# logger.net
KiCad netlist of a schematic drawn in EAGLE
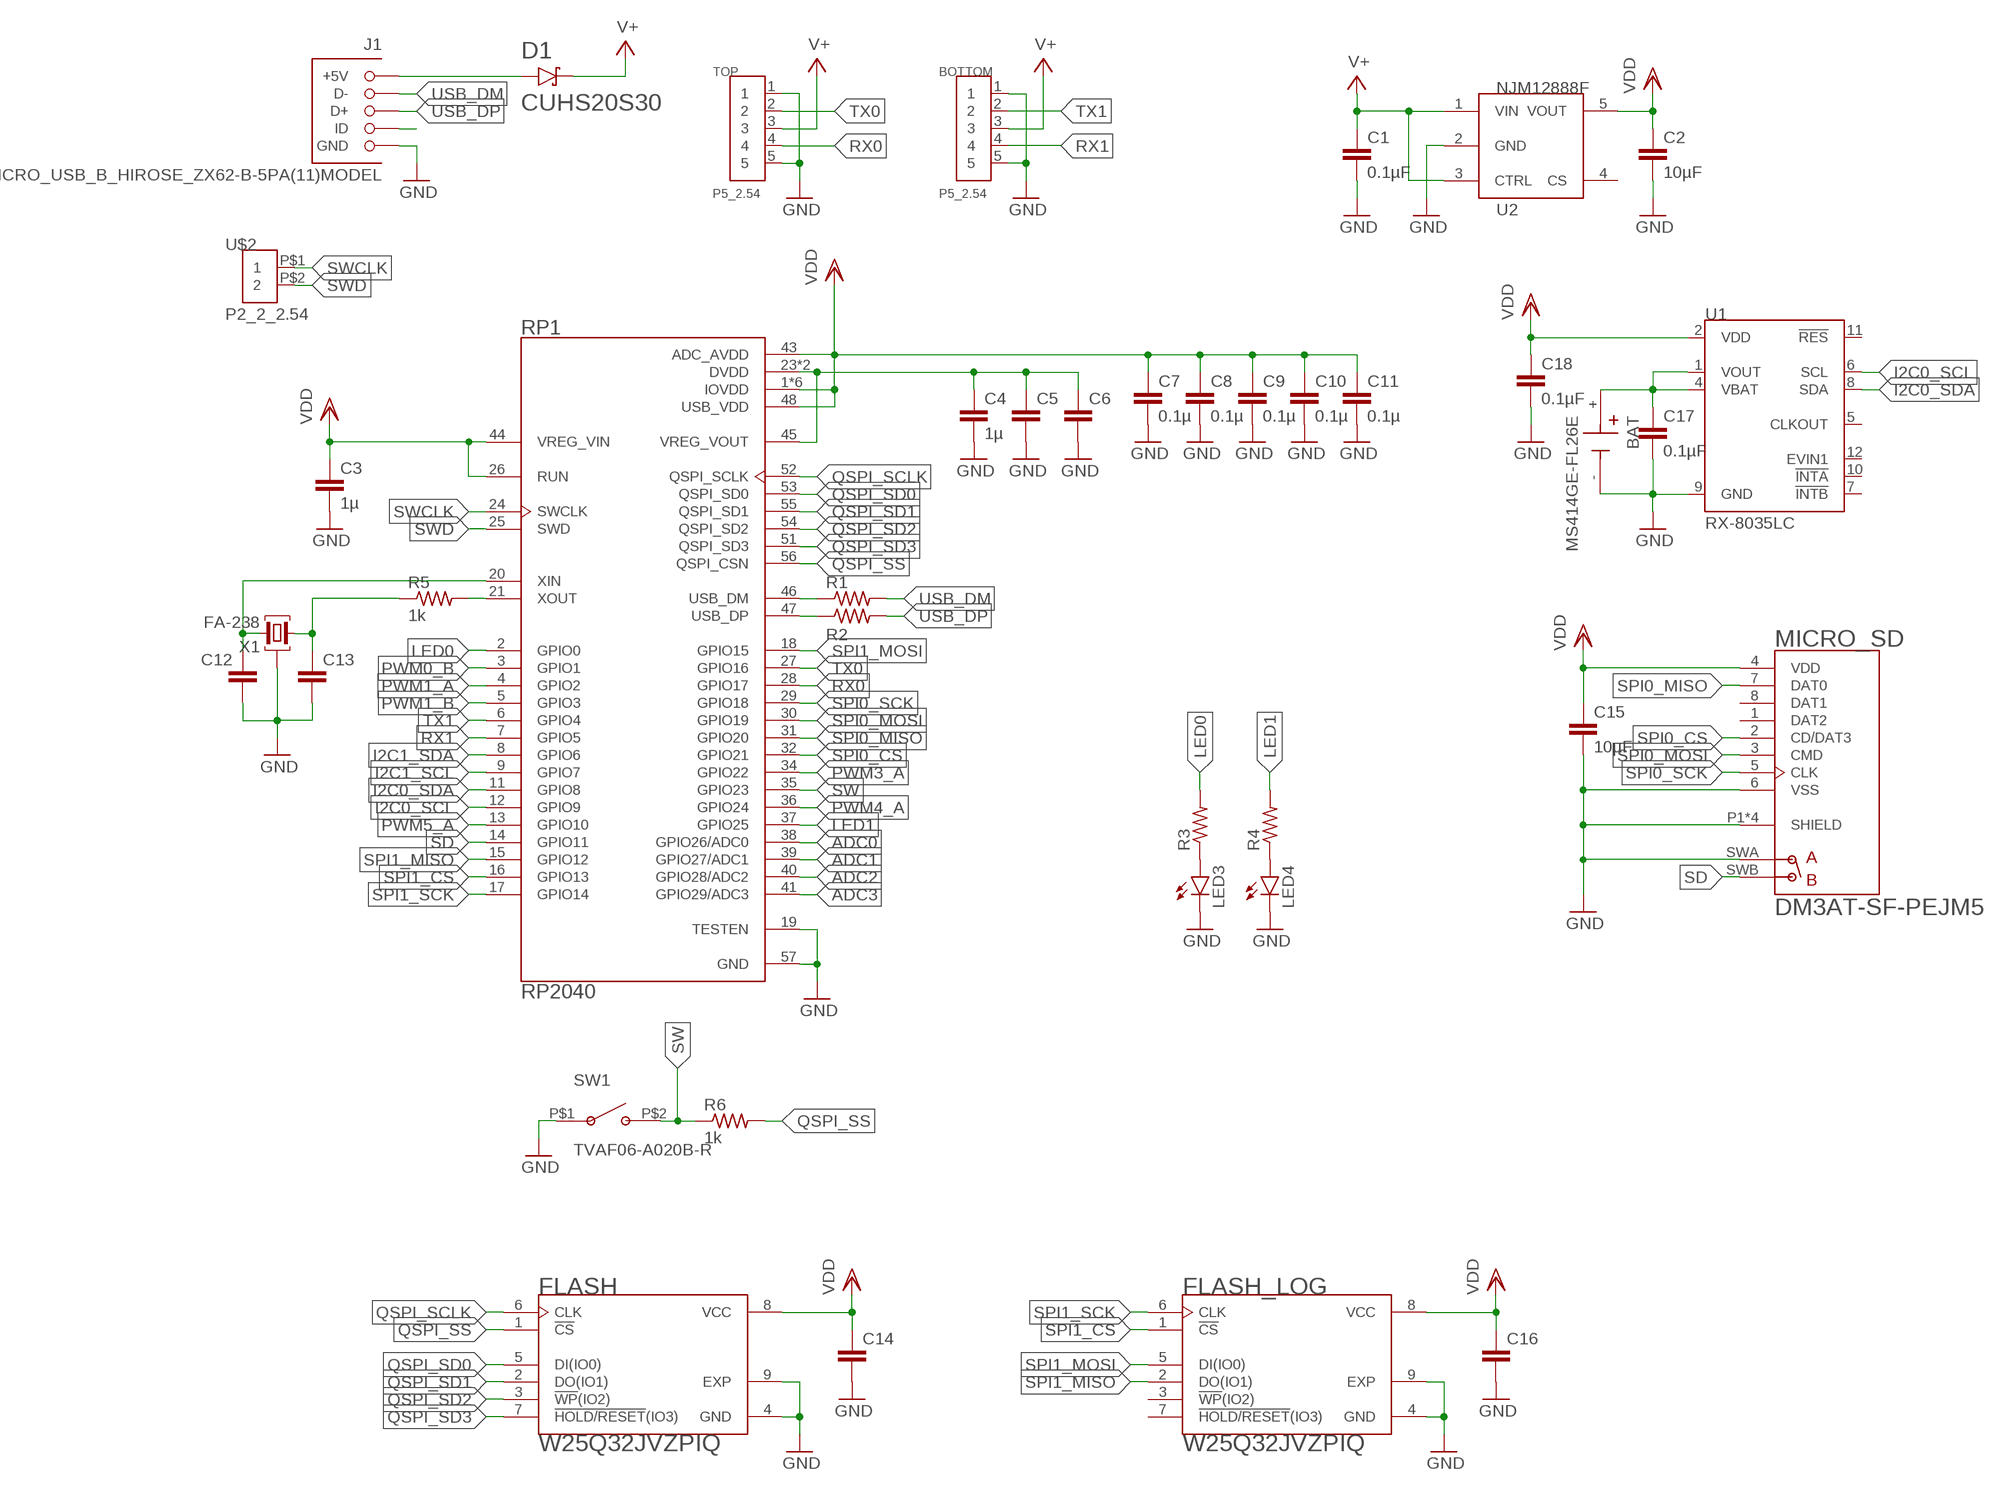
[diagram p0: schematic, sheet 1]

(export (version "E")
  (design (tool "Eeschema 10.0.6"))
  (components
    (comp (ref "BAT")
      (value "MS414GE-FL26E")
      (footprint "eagle-import:BAT_MS414GE-FL26E")
      (fields (field (name "MF") "Seiko"))
      (libsource (lib "eagle-import") (part "MS414GE-FL26E"))
    )
    (comp (ref "BOTTOM")
      (value "P5_2.54")
      (footprint "eagle-import:P5_2.54")
      (libsource (lib "eagle-import") (part "P5_2.54"))
    )
    (comp (ref "C1")
      (value "0.1µF")
      (footprint "eagle-import:C0402")
      (libsource (lib "eagle-import") (part "C-EUC0402"))
    )
    (comp (ref "C2")
      (value "10µF")
      (footprint "eagle-import:C0402")
      (libsource (lib "eagle-import") (part "C-EUC0402"))
    )
    (comp (ref "C3")
      (value "1µ")
      (footprint "eagle-import:C0402")
      (libsource (lib "eagle-import") (part "C-EUC0402"))
    )
    (comp (ref "C4")
      (value "1µ")
      (footprint "eagle-import:C0402")
      (libsource (lib "eagle-import") (part "C-EUC0402"))
    )
    (comp (ref "C5")
      (value "C-EUC0402")
      (footprint "eagle-import:C0402")
      (libsource (lib "eagle-import") (part "C-EUC0402"))
    )
    (comp (ref "C6")
      (value "C-EUC0402")
      (footprint "eagle-import:C0402")
      (libsource (lib "eagle-import") (part "C-EUC0402"))
    )
    (comp (ref "C7")
      (value "0.1µ")
      (footprint "eagle-import:C0402")
      (libsource (lib "eagle-import") (part "C-EUC0402"))
    )
    (comp (ref "C8")
      (value "0.1µ")
      (footprint "eagle-import:C0402")
      (libsource (lib "eagle-import") (part "C-EUC0402"))
    )
    (comp (ref "C9")
      (value "0.1µ")
      (footprint "eagle-import:C0402")
      (libsource (lib "eagle-import") (part "C-EUC0402"))
    )
    (comp (ref "C10")
      (value "0.1µ")
      (footprint "eagle-import:C0402")
      (libsource (lib "eagle-import") (part "C-EUC0402"))
    )
    (comp (ref "C11")
      (value "0.1µ")
      (footprint "eagle-import:C0402")
      (libsource (lib "eagle-import") (part "C-EUC0402"))
    )
    (comp (ref "C12")
      (value "C-EUC0402")
      (footprint "eagle-import:C0402")
      (libsource (lib "eagle-import") (part "C-EUC0402"))
    )
    (comp (ref "C13")
      (value "C-EUC0402")
      (footprint "eagle-import:C0402")
      (libsource (lib "eagle-import") (part "C-EUC0402"))
    )
    (comp (ref "C14")
      (value "C-EUC0402")
      (footprint "eagle-import:C0402")
      (libsource (lib "eagle-import") (part "C-EUC0402"))
    )
    (comp (ref "C15")
      (value "10µF")
      (footprint "eagle-import:C0402")
      (libsource (lib "eagle-import") (part "C-EUC0402"))
    )
    (comp (ref "C16")
      (value "C-EUC0402")
      (footprint "eagle-import:C0402")
      (libsource (lib "eagle-import") (part "C-EUC0402"))
    )
    (comp (ref "C17")
      (value "0.1µF")
      (footprint "eagle-import:C0402")
      (libsource (lib "eagle-import") (part "C-EUC0402"))
    )
    (comp (ref "C18")
      (value "0.1µF")
      (footprint "eagle-import:C0402")
      (libsource (lib "eagle-import") (part "C-EUC0402"))
    )
    (comp (ref "D1")
      (value "CUHS20S30")
      (footprint "eagle-import:CUHS20S30")
      (libsource (lib "eagle-import") (part "CUHS20S30"))
    )
    (comp (ref "FLASH")
      (value "W25Q32JVZPIQ")
      (footprint "eagle-import:SON127P600X500X80-9N")
      (fields (field (name "MF") "Winbond"))
      (libsource (lib "eagle-import") (part "W25Q32JVZPIQ"))
    )
    (comp (ref "FLASH_LOG")
      (value "W25Q32JVZPIQ")
      (footprint "eagle-import:SON127P600X500X80-9N")
      (fields (field (name "MF") "Winbond"))
      (libsource (lib "eagle-import") (part "W25Q32JVZPIQ"))
    )
    (comp (ref "J1")
      (value "MICRO_USB_B_HIROSE_ZX62-B-5PA(11)MODEL")
      (footprint "eagle-import:GHI-CONNECTORS_10118192-0001LF(MICRO-USB-B-AMPHENOL-FCI)")
      (libsource (lib "eagle-import") (part "MICRO_USB_B_HIROSE_ZX62-B-5PA(11)MODEL"))
    )
    (comp (ref "LED3")
      (value "LEDCHIPLED_0603")
      (footprint "eagle-import:CHIPLED_0603")
      (libsource (lib "eagle-import") (part "LEDCHIPLED_0603"))
    )
    (comp (ref "LED4")
      (value "LEDCHIPLED_0603")
      (footprint "eagle-import:CHIPLED_0603")
      (libsource (lib "eagle-import") (part "LEDCHIPLED_0603"))
    )
    (comp (ref "MICRO_SD")
      (value "DM3AT-SF-PEJM5")
      (footprint "eagle-import:HRS_DM3AT-SF-PEJM5")
      (fields (field (name "DIGI-KEY_PART_NUMBER") "HR1964CT-ND") (field (name "MF") "Hirose"))
      (libsource (lib "eagle-import") (part "DM3AT-SF-PEJM5"))
    )
    (comp (ref "R1")
      (value "R-US_R0402")
      (footprint "eagle-import:R0402")
      (libsource (lib "eagle-import") (part "R-US_R0402"))
    )
    (comp (ref "R2")
      (value "R-US_R0402")
      (footprint "eagle-import:R0402")
      (libsource (lib "eagle-import") (part "R-US_R0402"))
    )
    (comp (ref "R3")
      (value "R-US_R0402")
      (footprint "eagle-import:R0402")
      (libsource (lib "eagle-import") (part "R-US_R0402"))
    )
    (comp (ref "R4")
      (value "R-US_R0402")
      (footprint "eagle-import:R0402")
      (libsource (lib "eagle-import") (part "R-US_R0402"))
    )
    (comp (ref "R5")
      (value "1k")
      (footprint "eagle-import:R0402")
      (libsource (lib "eagle-import") (part "R-US_R0402"))
    )
    (comp (ref "R6")
      (value "1k")
      (footprint "eagle-import:R0402")
      (libsource (lib "eagle-import") (part "R-US_R0402"))
    )
    (comp (ref "RP1")
      (value "RP2040")
      (footprint "eagle-import:QFN40P700X700X90-57N")
      (fields (field (name "MF") "Raspberry Pi"))
      (libsource (lib "eagle-import") (part "RP2040"))
    )
    (comp (ref "SW1")
      (value "TVAF06-A020B-R")
      (footprint "eagle-import:TVAF06-A020B-R")
      (libsource (lib "eagle-import") (part "TVAF06-A020B-R"))
    )
    (comp (ref "TOP")
      (value "P5_2.54")
      (footprint "eagle-import:P5_2.54")
      (libsource (lib "eagle-import") (part "P5_2.54"))
    )
    (comp (ref "U$2")
      (value "P2_2_2.54")
      (footprint "eagle-import:P2_2.54")
      (libsource (lib "eagle-import") (part "P2_2_2.54"))
    )
    (comp (ref "U1")
      (value "RX-8035LC")
      (footprint "eagle-import:VSOJ12")
      (libsource (lib "eagle-import") (part "RX-8035LC"))
    )
    (comp (ref "U2")
      (value "NJM12888F")
      (footprint "eagle-import:SOT95P240X110-5N")
      (libsource (lib "eagle-import") (part "NJM12888F"))
    )
    (comp (ref "X1")
      (value "FA-238")
      (footprint "eagle-import:FA-238")
      (libsource (lib "eagle-import") (part "FA-238"))
    )
  )
  (nets
    (net (code "1") (name "ADC0") (class "Default")
      (node (ref "RP1") (pin "38") (pinfunction "GPIO26/ADC0_38") (pintype "bidirectional"))
    )
    (net (code "2") (name "ADC1") (class "Default")
      (node (ref "RP1") (pin "39") (pinfunction "GPIO27/ADC1_39") (pintype "bidirectional"))
    )
    (net (code "3") (name "ADC2") (class "Default")
      (node (ref "RP1") (pin "40") (pinfunction "GPIO28/ADC2_40") (pintype "bidirectional"))
    )
    (net (code "4") (name "ADC3") (class "Default")
      (node (ref "RP1") (pin "41") (pinfunction "GPIO29/ADC3_41") (pintype "bidirectional"))
    )
    (net (code "5") (name "GND") (class "Default")
      (node (ref "BAT") (pin "-") (pinfunction "-_-") (pintype "passive"))
      (node (ref "BOTTOM") (pin "1") (pinfunction "1_1") (pintype "bidirectional"))
      (node (ref "BOTTOM") (pin "5") (pinfunction "5_5") (pintype "bidirectional"))
      (node (ref "C1") (pin "2") (pinfunction "2_2") (pintype "passive"))
      (node (ref "C10") (pin "2") (pinfunction "2_2") (pintype "passive"))
      (node (ref "C11") (pin "2") (pinfunction "2_2") (pintype "passive"))
      (node (ref "C12") (pin "2") (pinfunction "2_2") (pintype "passive"))
      (node (ref "C13") (pin "2") (pinfunction "2_2") (pintype "passive"))
      (node (ref "C14") (pin "2") (pinfunction "2_2") (pintype "passive"))
      (node (ref "C15") (pin "2") (pinfunction "2_2") (pintype "passive"))
      (node (ref "C16") (pin "2") (pinfunction "2_2") (pintype "passive"))
      (node (ref "C17") (pin "2") (pinfunction "2_2") (pintype "passive"))
      (node (ref "C18") (pin "2") (pinfunction "2_2") (pintype "passive"))
      (node (ref "C2") (pin "2") (pinfunction "2_2") (pintype "passive"))
      (node (ref "C3") (pin "2") (pinfunction "2_2") (pintype "passive"))
      (node (ref "C4") (pin "2") (pinfunction "2_2") (pintype "passive"))
      (node (ref "C5") (pin "2") (pinfunction "2_2") (pintype "passive"))
      (node (ref "C6") (pin "2") (pinfunction "2_2") (pintype "passive"))
      (node (ref "C7") (pin "2") (pinfunction "2_2") (pintype "passive"))
      (node (ref "C8") (pin "2") (pinfunction "2_2") (pintype "passive"))
      (node (ref "C9") (pin "2") (pinfunction "2_2") (pintype "passive"))
      (node (ref "FLASH") (pin "4") (pinfunction "GND_4") (pintype "power_in"))
      (node (ref "FLASH") (pin "9") (pinfunction "EXP_9") (pintype "passive"))
      (node (ref "FLASH_LOG") (pin "4") (pinfunction "GND_4") (pintype "power_in"))
      (node (ref "FLASH_LOG") (pin "9") (pinfunction "EXP_9") (pintype "passive"))
      (node (ref "J1") (pin "CGND1") (pinfunction "GND_CGND1") (pintype "bidirectional"))
      (node (ref "J1") (pin "CGND2") (pinfunction "GND_CGND2") (pintype "bidirectional"))
      (node (ref "J1") (pin "CGND3") (pinfunction "GND_CGND3") (pintype "bidirectional"))
      (node (ref "J1") (pin "CGND4") (pinfunction "GND_CGND4") (pintype "bidirectional"))
      (node (ref "J1") (pin "CGND5") (pinfunction "GND_CGND5") (pintype "bidirectional"))
      (node (ref "J1") (pin "CGND6") (pinfunction "GND_CGND6") (pintype "bidirectional"))
      (node (ref "J1") (pin "GND") (pinfunction "GND_GND") (pintype "bidirectional"))
      (node (ref "LED3") (pin "C") (pinfunction "C_C") (pintype "passive"))
      (node (ref "LED4") (pin "C") (pinfunction "C_C") (pintype "passive"))
      (node (ref "MICRO_SD") (pin "6") (pinfunction "VSS_6") (pintype "power_in"))
      (node (ref "MICRO_SD") (pin "P1") (pinfunction "SHIELD_P1") (pintype "passive"))
      (node (ref "MICRO_SD") (pin "P2") (pinfunction "SHIELD_P2") (pintype "passive"))
      (node (ref "MICRO_SD") (pin "P3") (pinfunction "SHIELD_P3") (pintype "passive"))
      (node (ref "MICRO_SD") (pin "P4") (pinfunction "SHIELD_P4") (pintype "passive"))
      (node (ref "MICRO_SD") (pin "SWA") (pinfunction "A_SWA") (pintype "bidirectional"))
      (node (ref "RP1") (pin "19") (pinfunction "TESTEN_19") (pintype "passive"))
      (node (ref "RP1") (pin "57") (pinfunction "GND_57") (pintype "power_in"))
      (node (ref "SW1") (pin "P$1") (pinfunction "A_P$1") (pintype "bidirectional"))
      (node (ref "TOP") (pin "1") (pinfunction "1_1") (pintype "bidirectional"))
      (node (ref "TOP") (pin "5") (pinfunction "5_5") (pintype "bidirectional"))
      (node (ref "U1") (pin "9") (pinfunction "GND_9") (pintype "power_in"))
      (node (ref "U2") (pin "2") (pinfunction "GND_2") (pintype "power_in"))
      (node (ref "X1") (pin "2") (pinfunction "G_2") (pintype "passive"))
      (node (ref "X1") (pin "4") (pinfunction "G_4") (pintype "passive"))
    )
    (net (code "6") (name "I2C0_SCL") (class "Default")
      (node (ref "RP1") (pin "12") (pinfunction "GPIO9_12") (pintype "bidirectional"))
      (node (ref "U1") (pin "6") (pinfunction "SCL_6") (pintype "input"))
    )
    (net (code "7") (name "I2C0_SDA") (class "Default")
      (node (ref "RP1") (pin "11") (pinfunction "GPIO8_11") (pintype "bidirectional"))
      (node (ref "U1") (pin "8") (pinfunction "SDA_8") (pintype "bidirectional"))
    )
    (net (code "8") (name "I2C1_SCL") (class "Default")
      (node (ref "RP1") (pin "9") (pinfunction "GPIO7_9") (pintype "bidirectional"))
    )
    (net (code "9") (name "I2C1_SDA") (class "Default")
      (node (ref "RP1") (pin "8") (pinfunction "GPIO6_8") (pintype "bidirectional"))
    )
    (net (code "10") (name "LED0") (class "Default")
      (node (ref "R3") (pin "2") (pinfunction "2_2") (pintype "passive"))
      (node (ref "RP1") (pin "2") (pinfunction "GPIO0_2") (pintype "bidirectional"))
    )
    (net (code "11") (name "LED1") (class "Default")
      (node (ref "R4") (pin "2") (pinfunction "2_2") (pintype "passive"))
      (node (ref "RP1") (pin "37") (pinfunction "GPIO25_37") (pintype "bidirectional"))
    )
    (net (code "12") (name "Net-(C13-Pad1)") (class "Default")
      (node (ref "C13") (pin "1") (pinfunction "1_1") (pintype "passive"))
      (node (ref "R5") (pin "1") (pinfunction "1_1") (pintype "passive"))
      (node (ref "X1") (pin "1") (pinfunction "1_1") (pintype "passive"))
    )
    (net (code "13") (name "Net-(J1-+5V)") (class "Default")
      (node (ref "D1") (pin "A") (pinfunction "A_A") (pintype "bidirectional"))
      (node (ref "J1") (pin "VBUS") (pinfunction "+5V_VBUS") (pintype "bidirectional"))
    )
    (net (code "14") (name "Net-(LED3-PadA)") (class "Default")
      (node (ref "LED3") (pin "A") (pinfunction "A_A") (pintype "passive"))
      (node (ref "R3") (pin "1") (pinfunction "1_1") (pintype "passive"))
    )
    (net (code "15") (name "Net-(LED4-PadA)") (class "Default")
      (node (ref "LED4") (pin "A") (pinfunction "A_A") (pintype "passive"))
      (node (ref "R4") (pin "1") (pinfunction "1_1") (pintype "passive"))
    )
    (net (code "16") (name "Net-(RP1-USB_DM)") (class "Default")
      (node (ref "R1") (pin "1") (pinfunction "1_1") (pintype "passive"))
      (node (ref "RP1") (pin "46") (pinfunction "USB_DM_46") (pintype "bidirectional"))
    )
    (net (code "17") (name "Net-(RP1-USB_DP)") (class "Default")
      (node (ref "R2") (pin "1") (pinfunction "1_1") (pintype "passive"))
      (node (ref "RP1") (pin "47") (pinfunction "USB_DP_47") (pintype "bidirectional"))
    )
    (net (code "18") (name "Net-(RP1-VREG_VOUT)") (class "Default")
      (node (ref "C4") (pin "1") (pinfunction "1_1") (pintype "passive"))
      (node (ref "C5") (pin "1") (pinfunction "1_1") (pintype "passive"))
      (node (ref "C6") (pin "1") (pinfunction "1_1") (pintype "passive"))
      (node (ref "RP1") (pin "23") (pinfunction "DVDD_23") (pintype "power_in"))
      (node (ref "RP1") (pin "45") (pinfunction "VREG_VOUT_45") (pintype "output"))
      (node (ref "RP1") (pin "50") (pinfunction "DVDD_50") (pintype "power_in"))
    )
    (net (code "19") (name "Net-(RP1-XIN)") (class "Default")
      (node (ref "C12") (pin "1") (pinfunction "1_1") (pintype "passive"))
      (node (ref "RP1") (pin "20") (pinfunction "XIN_20") (pintype "input"))
      (node (ref "X1") (pin "3") (pinfunction "2_3") (pintype "passive"))
    )
    (net (code "20") (name "Net-(RP1-XOUT)") (class "Default")
      (node (ref "R5") (pin "2") (pinfunction "2_2") (pintype "passive"))
      (node (ref "RP1") (pin "21") (pinfunction "XOUT_21") (pintype "output"))
    )
    (net (code "21") (name "Net-(U1-VBAT)") (class "Default")
      (node (ref "BAT") (pin "+") (pinfunction "+_+") (pintype "passive"))
      (node (ref "C17") (pin "1") (pinfunction "1_1") (pintype "passive"))
      (node (ref "U1") (pin "1") (pinfunction "VOUT_1") (pintype "power_in"))
      (node (ref "U1") (pin "4") (pinfunction "VBAT_4") (pintype "power_in"))
    )
    (net (code "22") (name "PWM0_B") (class "Default")
      (node (ref "RP1") (pin "3") (pinfunction "GPIO1_3") (pintype "bidirectional"))
    )
    (net (code "23") (name "PWM1_A") (class "Default")
      (node (ref "RP1") (pin "4") (pinfunction "GPIO2_4") (pintype "bidirectional"))
    )
    (net (code "24") (name "PWM1_B") (class "Default")
      (node (ref "RP1") (pin "5") (pinfunction "GPIO3_5") (pintype "bidirectional"))
    )
    (net (code "25") (name "PWM3_A") (class "Default")
      (node (ref "RP1") (pin "34") (pinfunction "GPIO22_34") (pintype "bidirectional"))
    )
    (net (code "26") (name "PWM4_A") (class "Default")
      (node (ref "RP1") (pin "36") (pinfunction "GPIO24_36") (pintype "bidirectional"))
    )
    (net (code "27") (name "PWM5_A") (class "Default")
      (node (ref "RP1") (pin "13") (pinfunction "GPIO10_13") (pintype "bidirectional"))
    )
    (net (code "28") (name "QSPI_SCLK") (class "Default")
      (node (ref "FLASH") (pin "6") (pinfunction "CLK_6") (pintype "input"))
      (node (ref "RP1") (pin "52") (pinfunction "QSPI_SCLK_52") (pintype "bidirectional"))
    )
    (net (code "29") (name "QSPI_SD0") (class "Default")
      (node (ref "FLASH") (pin "5") (pinfunction "DI(IO0)_5") (pintype "bidirectional"))
      (node (ref "RP1") (pin "53") (pinfunction "QSPI_SD0_53") (pintype "bidirectional"))
    )
    (net (code "30") (name "QSPI_SD1") (class "Default")
      (node (ref "FLASH") (pin "2") (pinfunction "DO(IO1)_2") (pintype "bidirectional"))
      (node (ref "RP1") (pin "55") (pinfunction "QSPI_SD1_55") (pintype "bidirectional"))
    )
    (net (code "31") (name "QSPI_SD2") (class "Default")
      (node (ref "FLASH") (pin "3") (pinfunction "~{WP}(IO2)_3") (pintype "bidirectional"))
      (node (ref "RP1") (pin "54") (pinfunction "QSPI_SD2_54") (pintype "bidirectional"))
    )
    (net (code "32") (name "QSPI_SD3") (class "Default")
      (node (ref "FLASH") (pin "7") (pinfunction "~{HOLD/RESET}(IO3)_7") (pintype "bidirectional"))
      (node (ref "RP1") (pin "51") (pinfunction "QSPI_SD3_51") (pintype "bidirectional"))
    )
    (net (code "33") (name "QSPI_SS") (class "Default")
      (node (ref "FLASH") (pin "1") (pinfunction "~{CS}_1") (pintype "input"))
      (node (ref "R6") (pin "2") (pinfunction "2_2") (pintype "passive"))
      (node (ref "RP1") (pin "56") (pinfunction "QSPI_CSN_56") (pintype "bidirectional"))
    )
    (net (code "34") (name "RX0") (class "Default")
      (node (ref "RP1") (pin "28") (pinfunction "GPIO17_28") (pintype "bidirectional"))
      (node (ref "TOP") (pin "4") (pinfunction "4_4") (pintype "bidirectional"))
    )
    (net (code "35") (name "RX1") (class "Default")
      (node (ref "BOTTOM") (pin "4") (pinfunction "4_4") (pintype "bidirectional"))
      (node (ref "RP1") (pin "7") (pinfunction "GPIO5_7") (pintype "bidirectional"))
    )
    (net (code "36") (name "SD") (class "Default")
      (node (ref "MICRO_SD") (pin "SWB") (pinfunction "B_SWB") (pintype "bidirectional"))
      (node (ref "RP1") (pin "14") (pinfunction "GPIO11_14") (pintype "bidirectional"))
    )
    (net (code "37") (name "SPI0_CS") (class "Default")
      (node (ref "MICRO_SD") (pin "2") (pinfunction "CD/DAT3_2") (pintype "bidirectional"))
      (node (ref "RP1") (pin "32") (pinfunction "GPIO21_32") (pintype "bidirectional"))
    )
    (net (code "38") (name "SPI0_MISO") (class "Default")
      (node (ref "MICRO_SD") (pin "7") (pinfunction "DAT0_7") (pintype "bidirectional"))
      (node (ref "RP1") (pin "31") (pinfunction "GPIO20_31") (pintype "bidirectional"))
    )
    (net (code "39") (name "SPI0_MOSI") (class "Default")
      (node (ref "MICRO_SD") (pin "3") (pinfunction "CMD_3") (pintype "bidirectional"))
      (node (ref "RP1") (pin "30") (pinfunction "GPIO19_30") (pintype "bidirectional"))
    )
    (net (code "40") (name "SPI0_SCK") (class "Default")
      (node (ref "MICRO_SD") (pin "5") (pinfunction "CLK_5") (pintype "bidirectional"))
      (node (ref "RP1") (pin "29") (pinfunction "GPIO18_29") (pintype "bidirectional"))
    )
    (net (code "41") (name "SPI1_CS") (class "Default")
      (node (ref "FLASH_LOG") (pin "1") (pinfunction "~{CS}_1") (pintype "input"))
      (node (ref "RP1") (pin "16") (pinfunction "GPIO13_16") (pintype "bidirectional"))
    )
    (net (code "42") (name "SPI1_MISO") (class "Default")
      (node (ref "FLASH_LOG") (pin "2") (pinfunction "DO(IO1)_2") (pintype "bidirectional"))
      (node (ref "RP1") (pin "15") (pinfunction "GPIO12_15") (pintype "bidirectional"))
    )
    (net (code "43") (name "SPI1_MOSI") (class "Default")
      (node (ref "FLASH_LOG") (pin "5") (pinfunction "DI(IO0)_5") (pintype "bidirectional"))
      (node (ref "RP1") (pin "18") (pinfunction "GPIO15_18") (pintype "bidirectional"))
    )
    (net (code "44") (name "SPI1_SCK") (class "Default")
      (node (ref "FLASH_LOG") (pin "6") (pinfunction "CLK_6") (pintype "input"))
      (node (ref "RP1") (pin "17") (pinfunction "GPIO14_17") (pintype "bidirectional"))
    )
    (net (code "45") (name "SW") (class "Default")
      (node (ref "R6") (pin "1") (pinfunction "1_1") (pintype "passive"))
      (node (ref "RP1") (pin "35") (pinfunction "GPIO23_35") (pintype "bidirectional"))
      (node (ref "SW1") (pin "P$2") (pinfunction "B_P$2") (pintype "bidirectional"))
    )
    (net (code "46") (name "SWCLK") (class "Default")
      (node (ref "RP1") (pin "24") (pinfunction "SWCLK_24") (pintype "input"))
      (node (ref "U$2") (pin "P$1") (pinfunction "1_P$1") (pintype "bidirectional"))
    )
    (net (code "47") (name "SWD") (class "Default")
      (node (ref "RP1") (pin "25") (pinfunction "SWD_25") (pintype "bidirectional"))
      (node (ref "U$2") (pin "P$2") (pinfunction "2_P$2") (pintype "bidirectional"))
    )
    (net (code "48") (name "TX0") (class "Default")
      (node (ref "RP1") (pin "27") (pinfunction "GPIO16_27") (pintype "bidirectional"))
      (node (ref "TOP") (pin "2") (pinfunction "2_2") (pintype "bidirectional"))
    )
    (net (code "49") (name "TX1") (class "Default")
      (node (ref "BOTTOM") (pin "2") (pinfunction "2_2") (pintype "bidirectional"))
      (node (ref "RP1") (pin "6") (pinfunction "GPIO4_6") (pintype "bidirectional"))
    )
    (net (code "50") (name "USB_DM") (class "Default")
      (node (ref "J1") (pin "D-") (pinfunction "D-_D-") (pintype "bidirectional"))
      (node (ref "R1") (pin "2") (pinfunction "2_2") (pintype "passive"))
    )
    (net (code "51") (name "USB_DP") (class "Default")
      (node (ref "J1") (pin "D+") (pinfunction "D+_D+") (pintype "bidirectional"))
      (node (ref "R2") (pin "2") (pinfunction "2_2") (pintype "passive"))
    )
    (net (code "52") (name "V+") (class "Default")
      (node (ref "BOTTOM") (pin "3") (pinfunction "3_3") (pintype "bidirectional"))
      (node (ref "C1") (pin "1") (pinfunction "1_1") (pintype "passive"))
      (node (ref "D1") (pin "C") (pinfunction "C_C") (pintype "bidirectional"))
      (node (ref "TOP") (pin "3") (pinfunction "3_3") (pintype "bidirectional"))
      (node (ref "U2") (pin "1") (pinfunction "VIN_1") (pintype "power_in"))
      (node (ref "U2") (pin "3") (pinfunction "CTRL_3") (pintype "input"))
    )
    (net (code "53") (name "VDD") (class "Default")
      (node (ref "C10") (pin "1") (pinfunction "1_1") (pintype "passive"))
      (node (ref "C11") (pin "1") (pinfunction "1_1") (pintype "passive"))
      (node (ref "C14") (pin "1") (pinfunction "1_1") (pintype "passive"))
      (node (ref "C15") (pin "1") (pinfunction "1_1") (pintype "passive"))
      (node (ref "C16") (pin "1") (pinfunction "1_1") (pintype "passive"))
      (node (ref "C18") (pin "1") (pinfunction "1_1") (pintype "passive"))
      (node (ref "C2") (pin "1") (pinfunction "1_1") (pintype "passive"))
      (node (ref "C3") (pin "1") (pinfunction "1_1") (pintype "passive"))
      (node (ref "C7") (pin "1") (pinfunction "1_1") (pintype "passive"))
      (node (ref "C8") (pin "1") (pinfunction "1_1") (pintype "passive"))
      (node (ref "C9") (pin "1") (pinfunction "1_1") (pintype "passive"))
      (node (ref "FLASH") (pin "8") (pinfunction "VCC_8") (pintype "power_in"))
      (node (ref "FLASH_LOG") (pin "8") (pinfunction "VCC_8") (pintype "power_in"))
      (node (ref "MICRO_SD") (pin "4") (pinfunction "VDD_4") (pintype "power_in"))
      (node (ref "RP1") (pin "1") (pinfunction "IOVDD_1") (pintype "power_in"))
      (node (ref "RP1") (pin "10") (pinfunction "IOVDD_10") (pintype "power_in"))
      (node (ref "RP1") (pin "22") (pinfunction "IOVDD_22") (pintype "power_in"))
      (node (ref "RP1") (pin "26") (pinfunction "RUN_26") (pintype "input"))
      (node (ref "RP1") (pin "33") (pinfunction "IOVDD_33") (pintype "power_in"))
      (node (ref "RP1") (pin "42") (pinfunction "IOVDD_42") (pintype "power_in"))
      (node (ref "RP1") (pin "43") (pinfunction "ADC_AVDD_43") (pintype "power_in"))
      (node (ref "RP1") (pin "44") (pinfunction "VREG_VIN_44") (pintype "input"))
      (node (ref "RP1") (pin "48") (pinfunction "USB_VDD_48") (pintype "power_in"))
      (node (ref "RP1") (pin "49") (pinfunction "IOVDD_49") (pintype "power_in"))
      (node (ref "U1") (pin "2") (pinfunction "VDD_2") (pintype "power_in"))
      (node (ref "U2") (pin "5") (pinfunction "VOUT_5") (pintype "power_in"))
    )
    (net (code "54") (name "unconnected-(FLASH_LOG-~{HOLD{slash}RESET}(IO3)-Pad7)") (class "Default")
      (node (ref "FLASH_LOG") (pin "7") (pinfunction "~{HOLD/RESET}(IO3)_7") (pintype "bidirectional"))
    )
    (net (code "55") (name "unconnected-(FLASH_LOG-~{WP}(IO2)-Pad3)") (class "Default")
      (node (ref "FLASH_LOG") (pin "3") (pinfunction "~{WP}(IO2)_3") (pintype "bidirectional"))
    )
    (net (code "56") (name "unconnected-(J1-PadID)") (class "Default")
      (node (ref "J1") (pin "ID") (pinfunction "ID_ID") (pintype "bidirectional"))
    )
    (net (code "57") (name "unconnected-(MICRO_SD-DAT1-Pad8)") (class "Default")
      (node (ref "MICRO_SD") (pin "8") (pinfunction "DAT1_8") (pintype "bidirectional"))
    )
    (net (code "58") (name "unconnected-(MICRO_SD-DAT2-Pad1)") (class "Default")
      (node (ref "MICRO_SD") (pin "1") (pinfunction "DAT2_1") (pintype "bidirectional"))
    )
    (net (code "59") (name "unconnected-(U1-CLKOUT-Pad5)") (class "Default")
      (node (ref "U1") (pin "5") (pinfunction "CLKOUT_5") (pintype "output"))
    )
    (net (code "60") (name "unconnected-(U1-EVIN1-Pad12)") (class "Default")
      (node (ref "U1") (pin "12") (pinfunction "EVIN1_12") (pintype "input"))
    )
    (net (code "61") (name "unconnected-(U1-~{INTA}-Pad10)") (class "Default")
      (node (ref "U1") (pin "10") (pinfunction "~{INTA}_10") (pintype "output"))
    )
    (net (code "62") (name "unconnected-(U1-~{INTB}-Pad7)") (class "Default")
      (node (ref "U1") (pin "7") (pinfunction "~{INTB}_7") (pintype "output"))
    )
    (net (code "63") (name "unconnected-(U1-~{RES}-Pad11)") (class "Default")
      (node (ref "U1") (pin "11") (pinfunction "~{RES}_11") (pintype "output"))
    )
    (net (code "64") (name "unconnected-(U2-CS-Pad4)") (class "Default")
      (node (ref "U2") (pin "4") (pinfunction "CS_4") (pintype "input"))
    )
  )
)
